# c264-magic-cart-rev1.net
KiCad netlist of a schematic drawn in EAGLE
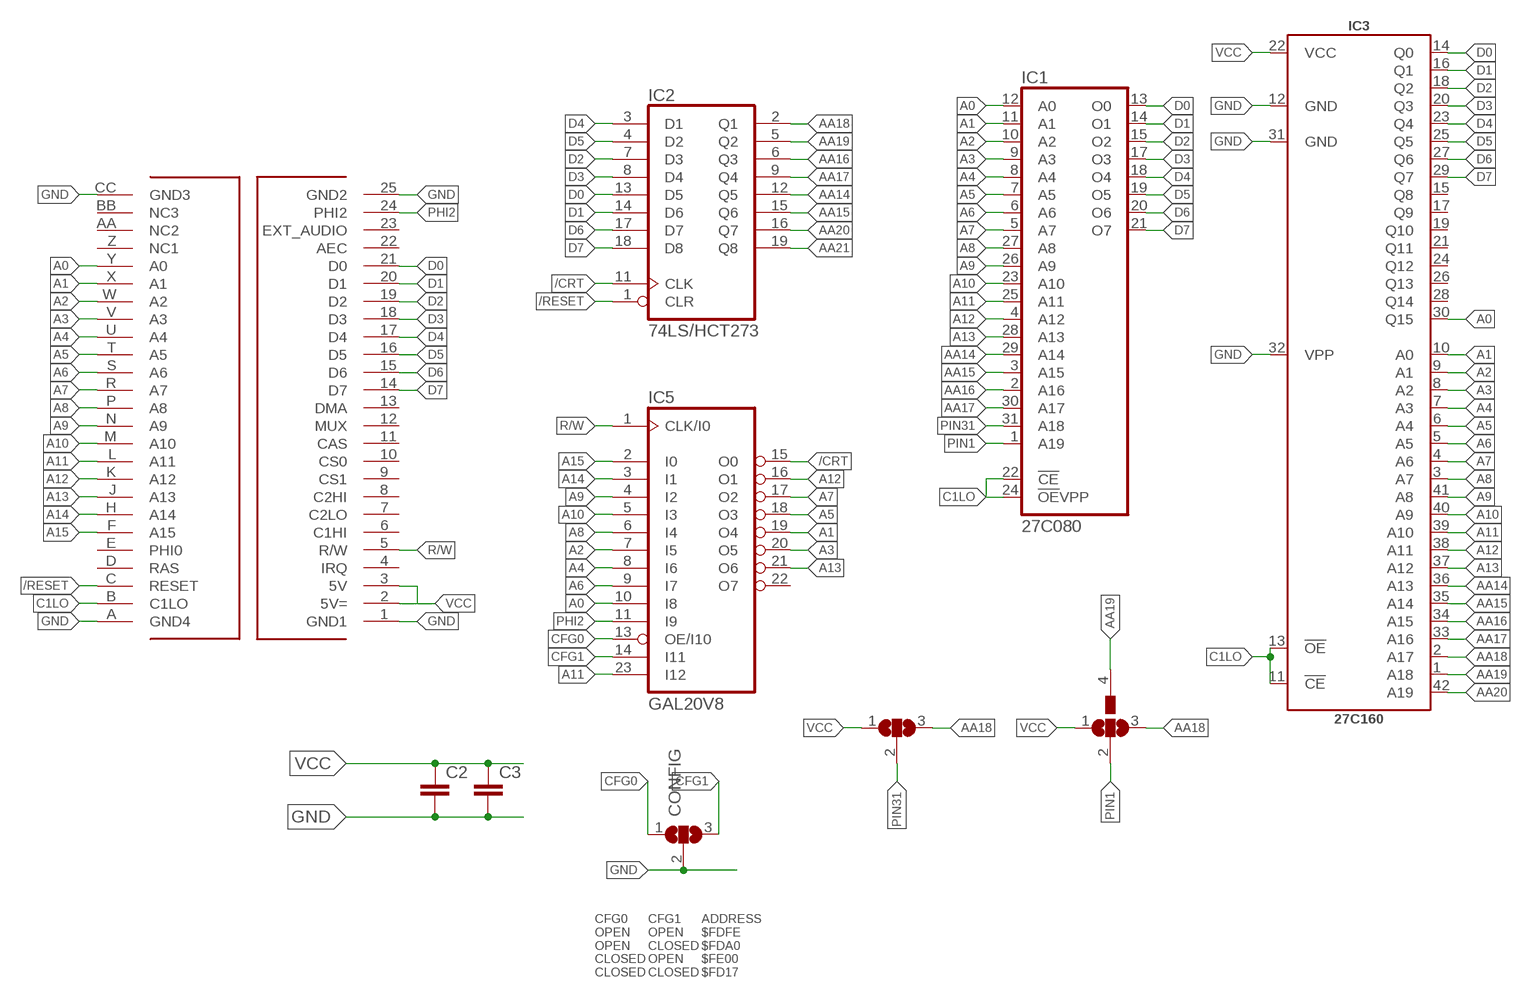
[diagram p0: schematic, sheet 1]

(export (version "E")
  (design (tool "Eeschema 10.0.6"))
  (components
    (comp (ref "C2")
      (value "C-EU025-024X044")
      (footprint "eagle-import:C025-024X044")
      (libsource (lib "eagle-import") (part "C-EU025-024X044"))
    )
    (comp (ref "C3")
      (value "C-EU025-024X044")
      (footprint "eagle-import:C025-024X044")
      (libsource (lib "eagle-import") (part "C-EU025-024X044"))
    )
    (comp (ref "CONFIG")
      (value "SJ2W")
      (footprint "eagle-import:SJ_2")
      (libsource (lib "eagle-import") (part "jumper_252_SJ2W"))
    )
    (comp (ref "IC1")
      (value "27C080")
      (footprint "eagle-import:DIL32")
      (fields (field (name "MPN") "AT27C080-90PU"))
      (libsource (lib "eagle-import") (part "27C08032P6"))
    )
    (comp (ref "IC2")
      (value "74LS/HCT273")
      (footprint "eagle-import:DIL20")
      (libsource (lib "eagle-import") (part "74273NHCT"))
    )
    (comp (ref "IC3")
      (value "27C160")
      (footprint "eagle-import:DIP42")
      (libsource (lib "eagle-import") (part "27C160_DIP42"))
    )
    (comp (ref "IC5")
      (value "GAL20V8")
      (footprint "eagle-import:DIL24-3")
      (fields (field (name "MF") "FARNELL") (field (name "MPN") "GAL20V8B-25QP"))
      (libsource (lib "eagle-import") (part "20V8"))
    )
    (comp (ref "SJ1")
      (value "SJ2W")
      (footprint "eagle-import:SJ_2")
      (libsource (lib "eagle-import") (part "SJ2W"))
    )
    (comp (ref "U$1")
      (value "C16_CARTRIDGE")
      (footprint "eagle-import:C16_CART")
      (libsource (lib "eagle-import") (part "C16_CARTRIDGE"))
    )
    (comp (ref "U$2")
      (value "SJ3")
      (footprint "eagle-import:SJ_3")
      (libsource (lib "eagle-import") (part "SJ3"))
    )
  )
  (nets
    (net (code "1") (name "A0") (class "Default")
      (node (ref "IC1") (pin "12") (pinfunction "A0_12") (pintype "input"))
      (node (ref "IC3") (pin "30") (pinfunction "Q15_30") (pintype "bidirectional"))
      (node (ref "IC5") (pin "10") (pinfunction "I8_10") (pintype "input"))
      (node (ref "U$1") (pin "Y") (pinfunction "A0_Y") (pintype "bidirectional"))
    )
    (net (code "2") (name "A1") (class "Default")
      (node (ref "IC1") (pin "11") (pinfunction "A1_11") (pintype "input"))
      (node (ref "IC3") (pin "10") (pinfunction "A0_10") (pintype "bidirectional"))
      (node (ref "IC5") (pin "19") (pinfunction "O4_19") (pintype "bidirectional"))
      (node (ref "U$1") (pin "X") (pinfunction "A1_X") (pintype "bidirectional"))
    )
    (net (code "3") (name "A2") (class "Default")
      (node (ref "IC1") (pin "10") (pinfunction "A2_10") (pintype "input"))
      (node (ref "IC3") (pin "9") (pinfunction "A1_9") (pintype "bidirectional"))
      (node (ref "IC5") (pin "7") (pinfunction "I5_7") (pintype "input"))
      (node (ref "U$1") (pin "W") (pinfunction "A2_W") (pintype "bidirectional"))
    )
    (net (code "4") (name "A3") (class "Default")
      (node (ref "IC1") (pin "9") (pinfunction "A3_9") (pintype "input"))
      (node (ref "IC3") (pin "8") (pinfunction "A2_8") (pintype "bidirectional"))
      (node (ref "IC5") (pin "20") (pinfunction "O5_20") (pintype "bidirectional"))
      (node (ref "U$1") (pin "V") (pinfunction "A3_V") (pintype "bidirectional"))
    )
    (net (code "5") (name "A4") (class "Default")
      (node (ref "IC1") (pin "8") (pinfunction "A4_8") (pintype "input"))
      (node (ref "IC3") (pin "7") (pinfunction "A3_7") (pintype "bidirectional"))
      (node (ref "IC5") (pin "8") (pinfunction "I6_8") (pintype "input"))
      (node (ref "U$1") (pin "U") (pinfunction "A4_U") (pintype "bidirectional"))
    )
    (net (code "6") (name "A5") (class "Default")
      (node (ref "IC1") (pin "7") (pinfunction "A5_7") (pintype "input"))
      (node (ref "IC3") (pin "6") (pinfunction "A4_6") (pintype "bidirectional"))
      (node (ref "IC5") (pin "18") (pinfunction "O3_18") (pintype "bidirectional"))
      (node (ref "U$1") (pin "T") (pinfunction "A5_T") (pintype "bidirectional"))
    )
    (net (code "7") (name "A6") (class "Default")
      (node (ref "IC1") (pin "6") (pinfunction "A6_6") (pintype "input"))
      (node (ref "IC3") (pin "5") (pinfunction "A5_5") (pintype "bidirectional"))
      (node (ref "IC5") (pin "9") (pinfunction "I7_9") (pintype "input"))
      (node (ref "U$1") (pin "S") (pinfunction "A6_S") (pintype "bidirectional"))
    )
    (net (code "8") (name "A7") (class "Default")
      (node (ref "IC1") (pin "5") (pinfunction "A7_5") (pintype "input"))
      (node (ref "IC3") (pin "4") (pinfunction "A6_4") (pintype "bidirectional"))
      (node (ref "IC5") (pin "17") (pinfunction "O2_17") (pintype "bidirectional"))
      (node (ref "U$1") (pin "R") (pinfunction "A7_R") (pintype "bidirectional"))
    )
    (net (code "9") (name "A8") (class "Default")
      (node (ref "IC1") (pin "27") (pinfunction "A8_27") (pintype "input"))
      (node (ref "IC3") (pin "3") (pinfunction "A7_3") (pintype "bidirectional"))
      (node (ref "IC5") (pin "6") (pinfunction "I4_6") (pintype "input"))
      (node (ref "U$1") (pin "P") (pinfunction "A8_P") (pintype "bidirectional"))
    )
    (net (code "10") (name "A9") (class "Default")
      (node (ref "IC1") (pin "26") (pinfunction "A9_26") (pintype "input"))
      (node (ref "IC3") (pin "41") (pinfunction "A8_41") (pintype "bidirectional"))
      (node (ref "IC5") (pin "4") (pinfunction "I2_4") (pintype "input"))
      (node (ref "U$1") (pin "N") (pinfunction "A9_N") (pintype "bidirectional"))
    )
    (net (code "11") (name "A10") (class "Default")
      (node (ref "IC1") (pin "23") (pinfunction "A10_23") (pintype "input"))
      (node (ref "IC3") (pin "40") (pinfunction "A9_40") (pintype "bidirectional"))
      (node (ref "IC5") (pin "5") (pinfunction "I3_5") (pintype "input"))
      (node (ref "U$1") (pin "M") (pinfunction "A10_M") (pintype "bidirectional"))
    )
    (net (code "12") (name "A11") (class "Default")
      (node (ref "IC1") (pin "25") (pinfunction "A11_25") (pintype "input"))
      (node (ref "IC3") (pin "39") (pinfunction "A10_39") (pintype "bidirectional"))
      (node (ref "IC5") (pin "23") (pinfunction "I12_23") (pintype "input"))
      (node (ref "U$1") (pin "L") (pinfunction "A11_L") (pintype "bidirectional"))
    )
    (net (code "13") (name "A12") (class "Default")
      (node (ref "IC1") (pin "4") (pinfunction "A12_4") (pintype "input"))
      (node (ref "IC3") (pin "38") (pinfunction "A11_38") (pintype "bidirectional"))
      (node (ref "IC5") (pin "16") (pinfunction "O1_16") (pintype "bidirectional"))
      (node (ref "U$1") (pin "K") (pinfunction "A12_K") (pintype "bidirectional"))
    )
    (net (code "14") (name "A13") (class "Default")
      (node (ref "IC1") (pin "28") (pinfunction "A13_28") (pintype "input"))
      (node (ref "IC3") (pin "37") (pinfunction "A12_37") (pintype "bidirectional"))
      (node (ref "IC5") (pin "21") (pinfunction "O6_21") (pintype "bidirectional"))
      (node (ref "U$1") (pin "J") (pinfunction "A13_J") (pintype "bidirectional"))
    )
    (net (code "15") (name "A14") (class "Default")
      (node (ref "IC5") (pin "3") (pinfunction "I1_3") (pintype "input"))
      (node (ref "U$1") (pin "H") (pinfunction "A14_H") (pintype "bidirectional"))
    )
    (net (code "16") (name "A15") (class "Default")
      (node (ref "IC5") (pin "2") (pinfunction "I0_2") (pintype "input"))
      (node (ref "U$1") (pin "F") (pinfunction "A15_F") (pintype "bidirectional"))
    )
    (net (code "17") (name "AA14") (class "Default")
      (node (ref "IC1") (pin "29") (pinfunction "A14_29") (pintype "input"))
      (node (ref "IC2") (pin "12") (pinfunction "Q5_12") (pintype "output"))
      (node (ref "IC3") (pin "36") (pinfunction "A13_36") (pintype "bidirectional"))
    )
    (net (code "18") (name "AA15") (class "Default")
      (node (ref "IC1") (pin "3") (pinfunction "A15_3") (pintype "input"))
      (node (ref "IC2") (pin "15") (pinfunction "Q6_15") (pintype "output"))
      (node (ref "IC3") (pin "35") (pinfunction "A14_35") (pintype "bidirectional"))
    )
    (net (code "19") (name "AA16") (class "Default")
      (node (ref "IC1") (pin "2") (pinfunction "A16_2") (pintype "input"))
      (node (ref "IC2") (pin "6") (pinfunction "Q3_6") (pintype "output"))
      (node (ref "IC3") (pin "34") (pinfunction "A15_34") (pintype "bidirectional"))
    )
    (net (code "20") (name "AA17") (class "Default")
      (node (ref "IC1") (pin "30") (pinfunction "A17_30") (pintype "input"))
      (node (ref "IC2") (pin "9") (pinfunction "Q4_9") (pintype "output"))
      (node (ref "IC3") (pin "33") (pinfunction "A16_33") (pintype "bidirectional"))
    )
    (net (code "21") (name "AA18") (class "Default")
      (node (ref "IC2") (pin "2") (pinfunction "Q1_2") (pintype "output"))
      (node (ref "IC3") (pin "2") (pinfunction "A17_2") (pintype "bidirectional"))
      (node (ref "SJ1") (pin "3") (pinfunction "3_3") (pintype "passive"))
      (node (ref "U$2") (pin "3") (pinfunction "3_3") (pintype "passive"))
    )
    (net (code "22") (name "AA19") (class "Default")
      (node (ref "IC2") (pin "5") (pinfunction "Q2_5") (pintype "output"))
      (node (ref "IC3") (pin "1") (pinfunction "A18_1") (pintype "bidirectional"))
      (node (ref "U$2") (pin "4") (pinfunction "4_4") (pintype "passive"))
    )
    (net (code "23") (name "AA20") (class "Default")
      (node (ref "IC2") (pin "16") (pinfunction "Q7_16") (pintype "output"))
      (node (ref "IC3") (pin "42") (pinfunction "A19_42") (pintype "bidirectional"))
    )
    (net (code "24") (name "AA21") (class "Default")
      (node (ref "IC2") (pin "19") (pinfunction "Q8_19") (pintype "output"))
    )
    (net (code "25") (name "C1LO") (class "Default")
      (node (ref "IC1") (pin "22") (pinfunction "~{CE}_22") (pintype "input"))
      (node (ref "IC1") (pin "24") (pinfunction "~{OE}VPP_24") (pintype "input"))
      (node (ref "IC3") (pin "11") (pinfunction "~{CE}_11") (pintype "bidirectional"))
      (node (ref "IC3") (pin "13") (pinfunction "~{OE}_13") (pintype "bidirectional"))
      (node (ref "U$1") (pin "B") (pinfunction "C1LO_B") (pintype "bidirectional"))
    )
    (net (code "26") (name "CFG0") (class "Default")
      (node (ref "CONFIG") (pin "1") (pinfunction "1_1") (pintype "passive"))
      (node (ref "IC5") (pin "13") (pinfunction "OE/I10_13") (pintype "input"))
    )
    (net (code "27") (name "CFG1") (class "Default")
      (node (ref "CONFIG") (pin "3") (pinfunction "3_3") (pintype "passive"))
      (node (ref "IC5") (pin "14") (pinfunction "I11_14") (pintype "input"))
    )
    (net (code "28") (name "D0") (class "Default")
      (node (ref "IC1") (pin "13") (pinfunction "O0_13") (pintype "tri_state"))
      (node (ref "IC2") (pin "13") (pinfunction "D5_13") (pintype "input"))
      (node (ref "IC3") (pin "14") (pinfunction "Q0_14") (pintype "bidirectional"))
      (node (ref "U$1") (pin "21") (pinfunction "D0_21") (pintype "bidirectional"))
    )
    (net (code "29") (name "D1") (class "Default")
      (node (ref "IC1") (pin "14") (pinfunction "O1_14") (pintype "tri_state"))
      (node (ref "IC2") (pin "14") (pinfunction "D6_14") (pintype "input"))
      (node (ref "IC3") (pin "16") (pinfunction "Q1_16") (pintype "bidirectional"))
      (node (ref "U$1") (pin "20") (pinfunction "D1_20") (pintype "bidirectional"))
    )
    (net (code "30") (name "D2") (class "Default")
      (node (ref "IC1") (pin "15") (pinfunction "O2_15") (pintype "tri_state"))
      (node (ref "IC2") (pin "7") (pinfunction "D3_7") (pintype "input"))
      (node (ref "IC3") (pin "18") (pinfunction "Q2_18") (pintype "bidirectional"))
      (node (ref "U$1") (pin "19") (pinfunction "D2_19") (pintype "bidirectional"))
    )
    (net (code "31") (name "D3") (class "Default")
      (node (ref "IC1") (pin "17") (pinfunction "O3_17") (pintype "tri_state"))
      (node (ref "IC2") (pin "8") (pinfunction "D4_8") (pintype "input"))
      (node (ref "IC3") (pin "20") (pinfunction "Q3_20") (pintype "bidirectional"))
      (node (ref "U$1") (pin "18") (pinfunction "D3_18") (pintype "bidirectional"))
    )
    (net (code "32") (name "D4") (class "Default")
      (node (ref "IC1") (pin "18") (pinfunction "O4_18") (pintype "tri_state"))
      (node (ref "IC2") (pin "3") (pinfunction "D1_3") (pintype "input"))
      (node (ref "IC3") (pin "23") (pinfunction "Q4_23") (pintype "bidirectional"))
      (node (ref "U$1") (pin "17") (pinfunction "D4_17") (pintype "bidirectional"))
    )
    (net (code "33") (name "D5") (class "Default")
      (node (ref "IC1") (pin "19") (pinfunction "O5_19") (pintype "tri_state"))
      (node (ref "IC2") (pin "4") (pinfunction "D2_4") (pintype "input"))
      (node (ref "IC3") (pin "25") (pinfunction "Q5_25") (pintype "bidirectional"))
      (node (ref "U$1") (pin "16") (pinfunction "D5_16") (pintype "bidirectional"))
    )
    (net (code "34") (name "D6") (class "Default")
      (node (ref "IC1") (pin "20") (pinfunction "O6_20") (pintype "tri_state"))
      (node (ref "IC2") (pin "17") (pinfunction "D7_17") (pintype "input"))
      (node (ref "IC3") (pin "27") (pinfunction "Q6_27") (pintype "bidirectional"))
      (node (ref "U$1") (pin "15") (pinfunction "D6_15") (pintype "bidirectional"))
    )
    (net (code "35") (name "D7") (class "Default")
      (node (ref "IC1") (pin "21") (pinfunction "O7_21") (pintype "tri_state"))
      (node (ref "IC2") (pin "18") (pinfunction "D8_18") (pintype "input"))
      (node (ref "IC3") (pin "29") (pinfunction "Q7_29") (pintype "bidirectional"))
      (node (ref "U$1") (pin "14") (pinfunction "D7_14") (pintype "bidirectional"))
    )
    (net (code "36") (name "GND") (class "Default")
      (node (ref "C2") (pin "2") (pinfunction "2_2") (pintype "passive"))
      (node (ref "C3") (pin "2") (pinfunction "2_2") (pintype "passive"))
      (node (ref "CONFIG") (pin "2") (pinfunction "2_2") (pintype "passive"))
      (node (ref "IC3") (pin "12") (pinfunction "GND_12") (pintype "power_in"))
      (node (ref "IC3") (pin "31") (pinfunction "GND_31") (pintype "power_in"))
      (node (ref "IC3") (pin "32") (pinfunction "VPP_32") (pintype "power_in"))
      (node (ref "U$1") (pin "1") (pinfunction "GND1_1") (pintype "bidirectional"))
      (node (ref "U$1") (pin "25") (pinfunction "GND2_25") (pintype "bidirectional"))
      (node (ref "U$1") (pin "A") (pinfunction "GND4_A") (pintype "bidirectional"))
      (node (ref "U$1") (pin "CC") (pinfunction "GND3_CC") (pintype "bidirectional"))
    )
    (net (code "37") (name "PHI2") (class "Default")
      (node (ref "IC5") (pin "11") (pinfunction "I9_11") (pintype "input"))
      (node (ref "U$1") (pin "24") (pinfunction "PHI2_24") (pintype "bidirectional"))
    )
    (net (code "38") (name "PIN1") (class "Default")
      (node (ref "IC1") (pin "1") (pinfunction "A19_1") (pintype "input"))
      (node (ref "U$2") (pin "2") (pinfunction "2_2") (pintype "passive"))
    )
    (net (code "39") (name "PIN31") (class "Default")
      (node (ref "IC1") (pin "31") (pinfunction "A18_31") (pintype "input"))
      (node (ref "SJ1") (pin "2") (pinfunction "2_2") (pintype "passive"))
    )
    (net (code "40") (name "R{slash}W") (class "Default")
      (node (ref "IC5") (pin "1") (pinfunction "CLK/I0_1") (pintype "input"))
      (node (ref "U$1") (pin "5") (pinfunction "R/W_5") (pintype "bidirectional"))
    )
    (net (code "41") (name "VCC") (class "Default")
      (node (ref "C2") (pin "1") (pinfunction "1_1") (pintype "passive"))
      (node (ref "C3") (pin "1") (pinfunction "1_1") (pintype "passive"))
      (node (ref "IC3") (pin "22") (pinfunction "VCC_22") (pintype "power_in"))
      (node (ref "SJ1") (pin "1") (pinfunction "1_1") (pintype "passive"))
      (node (ref "U$1") (pin "2") (pinfunction "5V=_2") (pintype "bidirectional"))
      (node (ref "U$1") (pin "3") (pinfunction "5V_3") (pintype "bidirectional"))
      (node (ref "U$2") (pin "1") (pinfunction "1_1") (pintype "passive"))
    )
    (net (code "42") (name "unconnected-(IC3-Q8-Pad15)") (class "Default")
      (node (ref "IC3") (pin "15") (pinfunction "Q8_15") (pintype "bidirectional"))
    )
    (net (code "43") (name "unconnected-(IC3-Q9-Pad17)") (class "Default")
      (node (ref "IC3") (pin "17") (pinfunction "Q9_17") (pintype "bidirectional"))
    )
    (net (code "44") (name "unconnected-(IC3-Q10-Pad19)") (class "Default")
      (node (ref "IC3") (pin "19") (pinfunction "Q10_19") (pintype "bidirectional"))
    )
    (net (code "45") (name "unconnected-(IC3-Q11-Pad21)") (class "Default")
      (node (ref "IC3") (pin "21") (pinfunction "Q11_21") (pintype "bidirectional"))
    )
    (net (code "46") (name "unconnected-(IC3-Q12-Pad24)") (class "Default")
      (node (ref "IC3") (pin "24") (pinfunction "Q12_24") (pintype "bidirectional"))
    )
    (net (code "47") (name "unconnected-(IC3-Q13-Pad26)") (class "Default")
      (node (ref "IC3") (pin "26") (pinfunction "Q13_26") (pintype "bidirectional"))
    )
    (net (code "48") (name "unconnected-(IC3-Q14-Pad28)") (class "Default")
      (node (ref "IC3") (pin "28") (pinfunction "Q14_28") (pintype "bidirectional"))
    )
    (net (code "49") (name "unconnected-(IC5A-O7-Pad22)") (class "Default")
      (node (ref "IC5") (pin "22") (pinfunction "O7_22") (pintype "bidirectional"))
    )
    (net (code "50") (name "unconnected-(U$1-AEC-Pad22)") (class "Default")
      (node (ref "U$1") (pin "22") (pinfunction "AEC_22") (pintype "bidirectional"))
    )
    (net (code "51") (name "unconnected-(U$1-C1HI-Pad6)") (class "Default")
      (node (ref "U$1") (pin "6") (pinfunction "C1HI_6") (pintype "bidirectional"))
    )
    (net (code "52") (name "unconnected-(U$1-C2HI-Pad8)") (class "Default")
      (node (ref "U$1") (pin "8") (pinfunction "C2HI_8") (pintype "bidirectional"))
    )
    (net (code "53") (name "unconnected-(U$1-C2LO-Pad7)") (class "Default")
      (node (ref "U$1") (pin "7") (pinfunction "C2LO_7") (pintype "bidirectional"))
    )
    (net (code "54") (name "unconnected-(U$1-CAS-Pad11)") (class "Default")
      (node (ref "U$1") (pin "11") (pinfunction "CAS_11") (pintype "bidirectional"))
    )
    (net (code "55") (name "unconnected-(U$1-CS0-Pad10)") (class "Default")
      (node (ref "U$1") (pin "10") (pinfunction "CS0_10") (pintype "bidirectional"))
    )
    (net (code "56") (name "unconnected-(U$1-CS1-Pad9)") (class "Default")
      (node (ref "U$1") (pin "9") (pinfunction "CS1_9") (pintype "bidirectional"))
    )
    (net (code "57") (name "unconnected-(U$1-DMA-Pad13)") (class "Default")
      (node (ref "U$1") (pin "13") (pinfunction "DMA_13") (pintype "bidirectional"))
    )
    (net (code "58") (name "unconnected-(U$1-EXT_AUDIO-Pad23)") (class "Default")
      (node (ref "U$1") (pin "23") (pinfunction "EXT_AUDIO_23") (pintype "bidirectional"))
    )
    (net (code "59") (name "unconnected-(U$1-IRQ-Pad4)") (class "Default")
      (node (ref "U$1") (pin "4") (pinfunction "IRQ_4") (pintype "bidirectional"))
    )
    (net (code "60") (name "unconnected-(U$1-MUX-Pad12)") (class "Default")
      (node (ref "U$1") (pin "12") (pinfunction "MUX_12") (pintype "bidirectional"))
    )
    (net (code "61") (name "unconnected-(U$1-NC1-PadZ)") (class "Default")
      (node (ref "U$1") (pin "Z") (pinfunction "NC1_Z") (pintype "bidirectional"))
    )
    (net (code "62") (name "unconnected-(U$1-NC2-PadAA)") (class "Default")
      (node (ref "U$1") (pin "AA") (pinfunction "NC2_AA") (pintype "bidirectional"))
    )
    (net (code "63") (name "unconnected-(U$1-NC3-PadBB)") (class "Default")
      (node (ref "U$1") (pin "BB") (pinfunction "NC3_BB") (pintype "bidirectional"))
    )
    (net (code "64") (name "unconnected-(U$1-PHI0-PadE)") (class "Default")
      (node (ref "U$1") (pin "E") (pinfunction "PHI0_E") (pintype "bidirectional"))
    )
    (net (code "65") (name "unconnected-(U$1-RAS-PadD)") (class "Default")
      (node (ref "U$1") (pin "D") (pinfunction "RAS_D") (pintype "bidirectional"))
    )
    (net (code "66") (name "{slash}CRT") (class "Default")
      (node (ref "IC2") (pin "11") (pinfunction "CLK_11") (pintype "input"))
      (node (ref "IC5") (pin "15") (pinfunction "O0_15") (pintype "bidirectional"))
    )
    (net (code "67") (name "{slash}RESET") (class "Default")
      (node (ref "IC2") (pin "1") (pinfunction "CLR_1") (pintype "input"))
      (node (ref "U$1") (pin "C") (pinfunction "RESET_C") (pintype "bidirectional"))
    )
  )
)
